# stm32h405-braids-panel.net
KiCad netlist of a schematic drawn in EAGLE
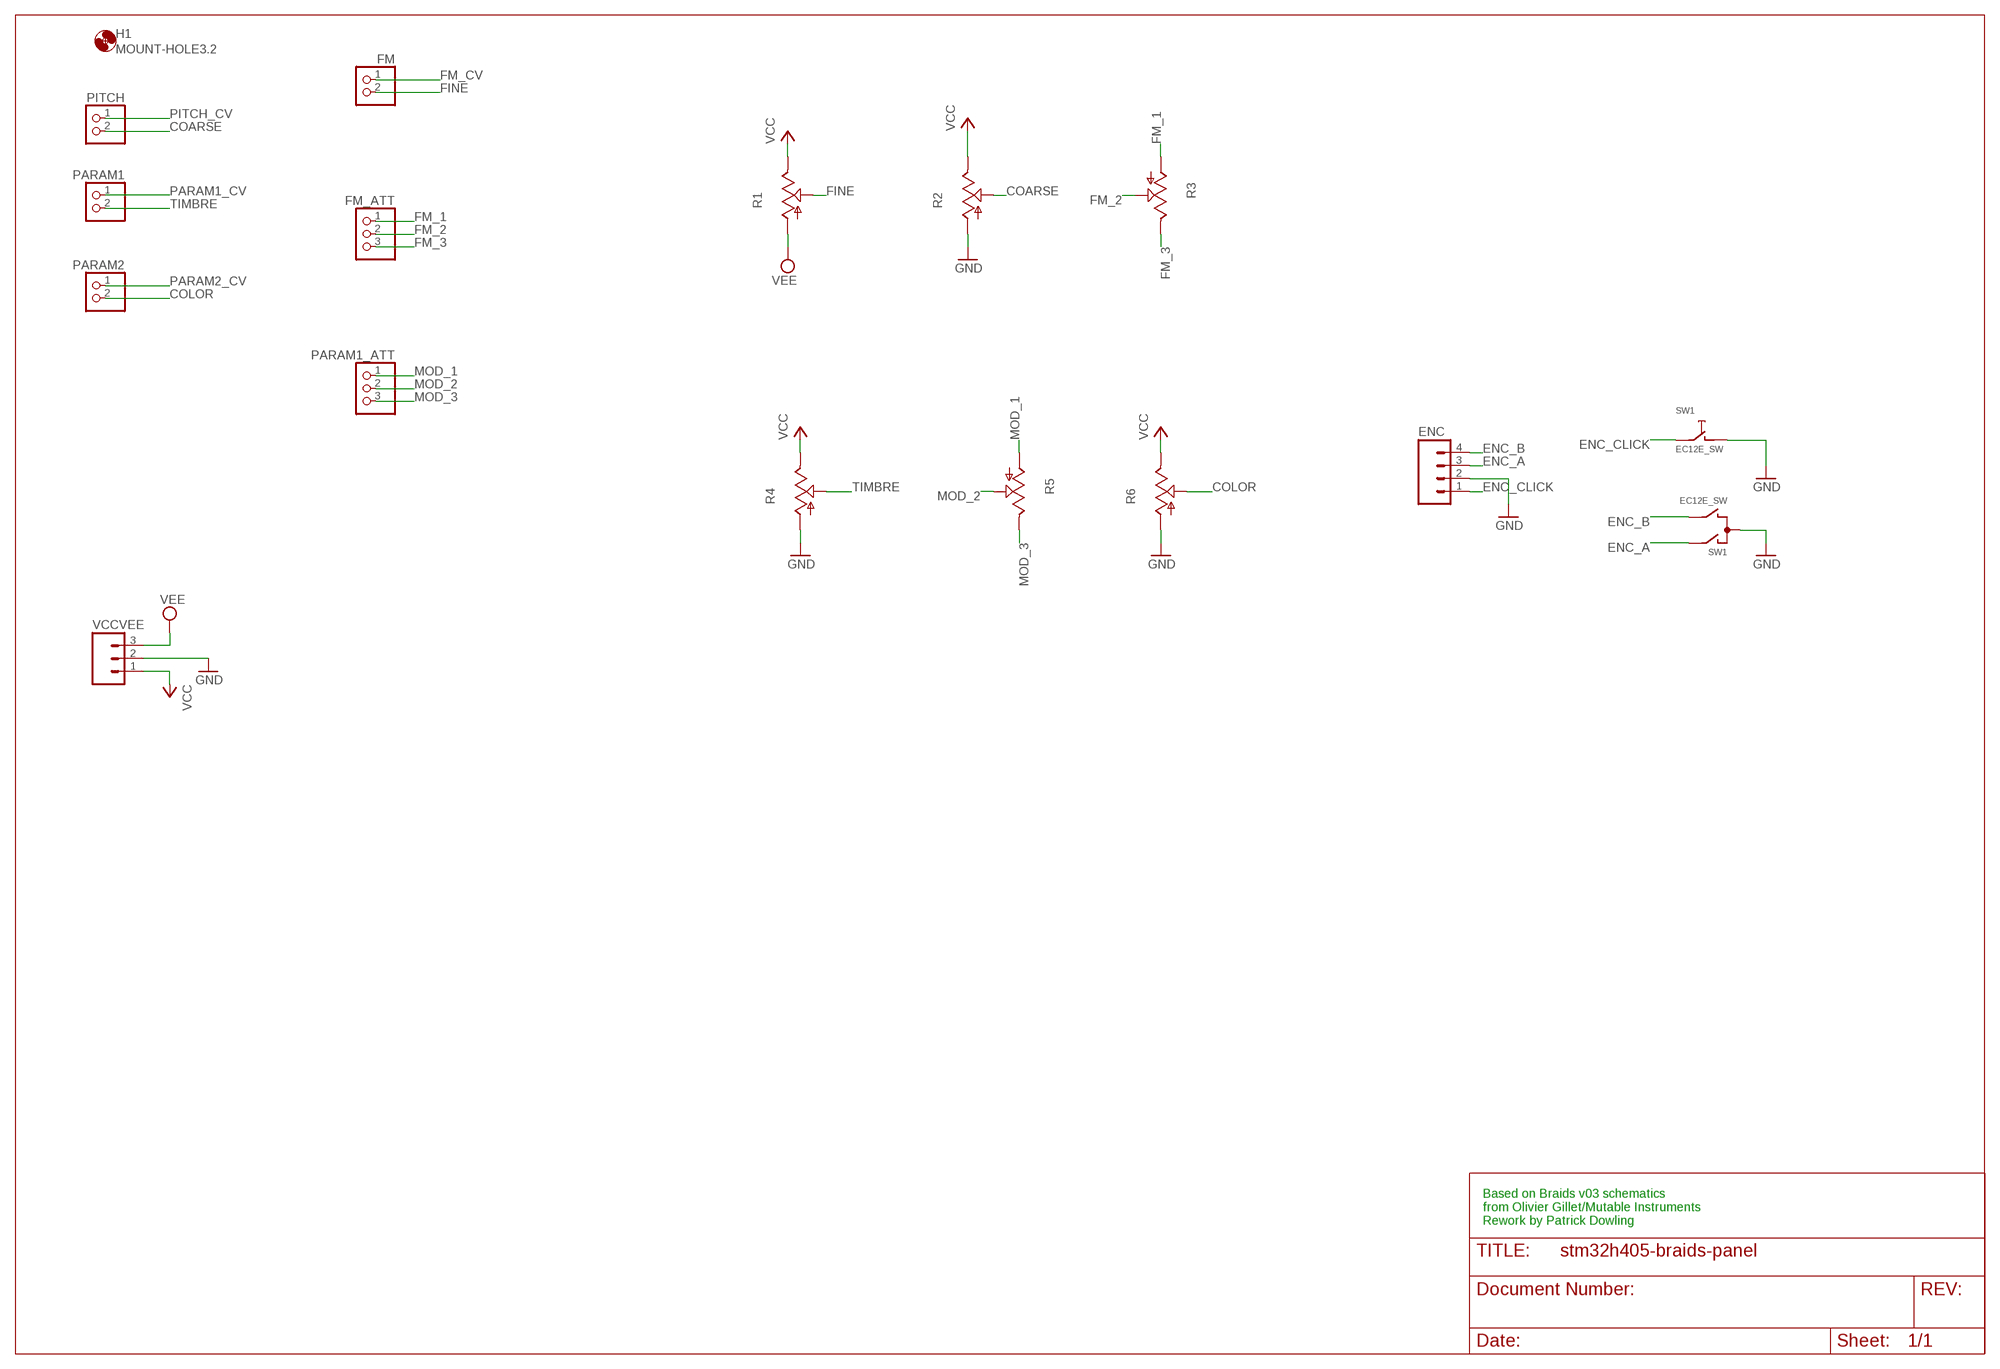
[diagram p0: schematic, sheet 1]

(export (version "E")
  (design (tool "Eeschema 10.0.6"))
  (components
    (comp (ref "ENC")
      (value "M04PTH")
      (footprint "eagle-import:1X04")
      (libsource (lib "eagle-import") (part "M04PTH"))
    )
    (comp (ref "FM")
      (value "PINHD-1X2")
      (footprint "eagle-import:1X02")
      (libsource (lib "eagle-import") (part "PINHD-1X2"))
    )
    (comp (ref "FM_ATT")
      (value "PINHD-1X3")
      (footprint "eagle-import:1X03")
      (libsource (lib "eagle-import") (part "PINHD-1X3"))
    )
    (comp (ref "H1")
      (value "MOUNT-HOLE3.2")
      (footprint "eagle-import:3,2")
      (libsource (lib "eagle-import") (part "MOUNT-HOLE3.2"))
    )
    (comp (ref "PARAM1")
      (value "PINHD-1X2")
      (footprint "eagle-import:1X02")
      (libsource (lib "eagle-import") (part "PINHD-1X2"))
    )
    (comp (ref "PARAM1_ATT")
      (value "PINHD-1X3")
      (footprint "eagle-import:1X03")
      (libsource (lib "eagle-import") (part "PINHD-1X3"))
    )
    (comp (ref "PARAM2")
      (value "PINHD-1X2")
      (footprint "eagle-import:1X02")
      (libsource (lib "eagle-import") (part "PINHD-1X2"))
    )
    (comp (ref "PITCH")
      (value "PINHD-1X2")
      (footprint "eagle-import:1X02")
      (libsource (lib "eagle-import") (part "PINHD-1X2"))
    )
    (comp (ref "R1")
      (value "POT_USVERTICAL_PS")
      (footprint "eagle-import:ALPS_POT_VERTICAL_PS")
      (libsource (lib "eagle-import") (part "POT_USVERTICAL_PS"))
    )
    (comp (ref "R2")
      (value "POT_USVERTICAL_PS")
      (footprint "eagle-import:ALPS_POT_VERTICAL_PS")
      (libsource (lib "eagle-import") (part "POT_USVERTICAL_PS"))
    )
    (comp (ref "R3")
      (value "POT_USVERTICAL_PS")
      (footprint "eagle-import:ALPS_POT_VERTICAL_PS")
      (libsource (lib "eagle-import") (part "POT_USVERTICAL_PS"))
    )
    (comp (ref "R4")
      (value "POT_USVERTICAL_PS")
      (footprint "eagle-import:ALPS_POT_VERTICAL_PS")
      (libsource (lib "eagle-import") (part "POT_USVERTICAL_PS"))
    )
    (comp (ref "R5")
      (value "POT_USVERTICAL_PS")
      (footprint "eagle-import:ALPS_POT_VERTICAL_PS")
      (libsource (lib "eagle-import") (part "POT_USVERTICAL_PS"))
    )
    (comp (ref "R6")
      (value "POT_USVERTICAL_PS")
      (footprint "eagle-import:ALPS_POT_VERTICAL_PS")
      (libsource (lib "eagle-import") (part "POT_USVERTICAL_PS"))
    )
    (comp (ref "SW1")
      (value "EC12E_SW")
      (footprint "eagle-import:ALPS_EC12E_SW")
      (libsource (lib "eagle-import") (part "EC12E_SW"))
    )
    (comp (ref "VCCVEE")
      (value "M031X03_NO_SILK")
      (footprint "eagle-import:1X03_NO_SILK")
      (libsource (lib "eagle-import") (part "M031X03_NO_SILK"))
    )
  )
  (nets
    (net (code "1") (name "/COARSE") (class "Default")
      (node (ref "PITCH") (pin "2") (pinfunction "2_2") (pintype "passive"))
      (node (ref "R2") (pin "P$2") (pinfunction "S_P$2") (pintype "passive"))
    )
    (net (code "2") (name "/COLOR") (class "Default")
      (node (ref "PARAM2") (pin "2") (pinfunction "2_2") (pintype "passive"))
      (node (ref "R6") (pin "P$2") (pinfunction "S_P$2") (pintype "passive"))
    )
    (net (code "3") (name "/ENC_A") (class "Default")
      (node (ref "ENC") (pin "3") (pinfunction "3_3") (pintype "passive"))
      (node (ref "SW1") (pin "A") (pinfunction "A_A") (pintype "passive"))
    )
    (net (code "4") (name "/ENC_B") (class "Default")
      (node (ref "ENC") (pin "4") (pinfunction "4_4") (pintype "passive"))
      (node (ref "SW1") (pin "B") (pinfunction "B_B") (pintype "passive"))
    )
    (net (code "5") (name "/ENC_CLICK") (class "Default")
      (node (ref "ENC") (pin "1") (pinfunction "1_1") (pintype "passive"))
      (node (ref "SW1") (pin "E") (pinfunction "2_E") (pintype "passive"))
    )
    (net (code "6") (name "/FINE") (class "Default")
      (node (ref "FM") (pin "2") (pinfunction "2_2") (pintype "passive"))
      (node (ref "R1") (pin "P$2") (pinfunction "S_P$2") (pintype "passive"))
    )
    (net (code "7") (name "/FM_1") (class "Default")
      (node (ref "FM_ATT") (pin "1") (pinfunction "1_1") (pintype "passive"))
      (node (ref "R3") (pin "P$3") (pinfunction "A_P$3") (pintype "passive"))
    )
    (net (code "8") (name "/FM_2") (class "Default")
      (node (ref "FM_ATT") (pin "2") (pinfunction "2_2") (pintype "passive"))
      (node (ref "R3") (pin "P$2") (pinfunction "S_P$2") (pintype "passive"))
    )
    (net (code "9") (name "/FM_3") (class "Default")
      (node (ref "FM_ATT") (pin "3") (pinfunction "3_3") (pintype "passive"))
      (node (ref "R3") (pin "P$1") (pinfunction "E_P$1") (pintype "passive"))
    )
    (net (code "10") (name "/FM_CV") (class "Default")
      (node (ref "FM") (pin "1") (pinfunction "1_1") (pintype "passive"))
    )
    (net (code "11") (name "/MOD_1") (class "Default")
      (node (ref "PARAM1_ATT") (pin "1") (pinfunction "1_1") (pintype "passive"))
      (node (ref "R5") (pin "P$3") (pinfunction "A_P$3") (pintype "passive"))
    )
    (net (code "12") (name "/MOD_2") (class "Default")
      (node (ref "PARAM1_ATT") (pin "2") (pinfunction "2_2") (pintype "passive"))
      (node (ref "R5") (pin "P$2") (pinfunction "S_P$2") (pintype "passive"))
    )
    (net (code "13") (name "/MOD_3") (class "Default")
      (node (ref "PARAM1_ATT") (pin "3") (pinfunction "3_3") (pintype "passive"))
      (node (ref "R5") (pin "P$1") (pinfunction "E_P$1") (pintype "passive"))
    )
    (net (code "14") (name "/PARAM1_CV") (class "Default")
      (node (ref "PARAM1") (pin "1") (pinfunction "1_1") (pintype "passive"))
    )
    (net (code "15") (name "/PARAM2_CV") (class "Default")
      (node (ref "PARAM2") (pin "1") (pinfunction "1_1") (pintype "passive"))
    )
    (net (code "16") (name "/PITCH_CV") (class "Default")
      (node (ref "PITCH") (pin "1") (pinfunction "1_1") (pintype "passive"))
    )
    (net (code "17") (name "/TIMBRE") (class "Default")
      (node (ref "PARAM1") (pin "2") (pinfunction "2_2") (pintype "passive"))
      (node (ref "R4") (pin "P$2") (pinfunction "S_P$2") (pintype "passive"))
    )
    (net (code "18") (name "GND") (class "Default")
      (node (ref "ENC") (pin "2") (pinfunction "2_2") (pintype "passive"))
      (node (ref "R2") (pin "P$3") (pinfunction "A_P$3") (pintype "passive"))
      (node (ref "R4") (pin "P$3") (pinfunction "A_P$3") (pintype "passive"))
      (node (ref "R6") (pin "P$3") (pinfunction "A_P$3") (pintype "passive"))
      (node (ref "SW1") (pin "C") (pinfunction "C_C") (pintype "passive"))
      (node (ref "SW1") (pin "D") (pinfunction "1_D") (pintype "passive"))
      (node (ref "VCCVEE") (pin "2") (pinfunction "2_2") (pintype "passive"))
    )
    (net (code "19") (name "VCC") (class "Default")
      (node (ref "R1") (pin "P$1") (pinfunction "E_P$1") (pintype "passive"))
      (node (ref "R2") (pin "P$1") (pinfunction "E_P$1") (pintype "passive"))
      (node (ref "R4") (pin "P$1") (pinfunction "E_P$1") (pintype "passive"))
      (node (ref "R6") (pin "P$1") (pinfunction "E_P$1") (pintype "passive"))
      (node (ref "VCCVEE") (pin "1") (pinfunction "1_1") (pintype "passive"))
    )
    (net (code "20") (name "VEE") (class "Default")
      (node (ref "R1") (pin "P$3") (pinfunction "A_P$3") (pintype "passive"))
      (node (ref "VCCVEE") (pin "3") (pinfunction "3_3") (pintype "passive"))
    )
  )
)
